# mcu.net
KiCad netlist of a schematic drawn in Altium Designer
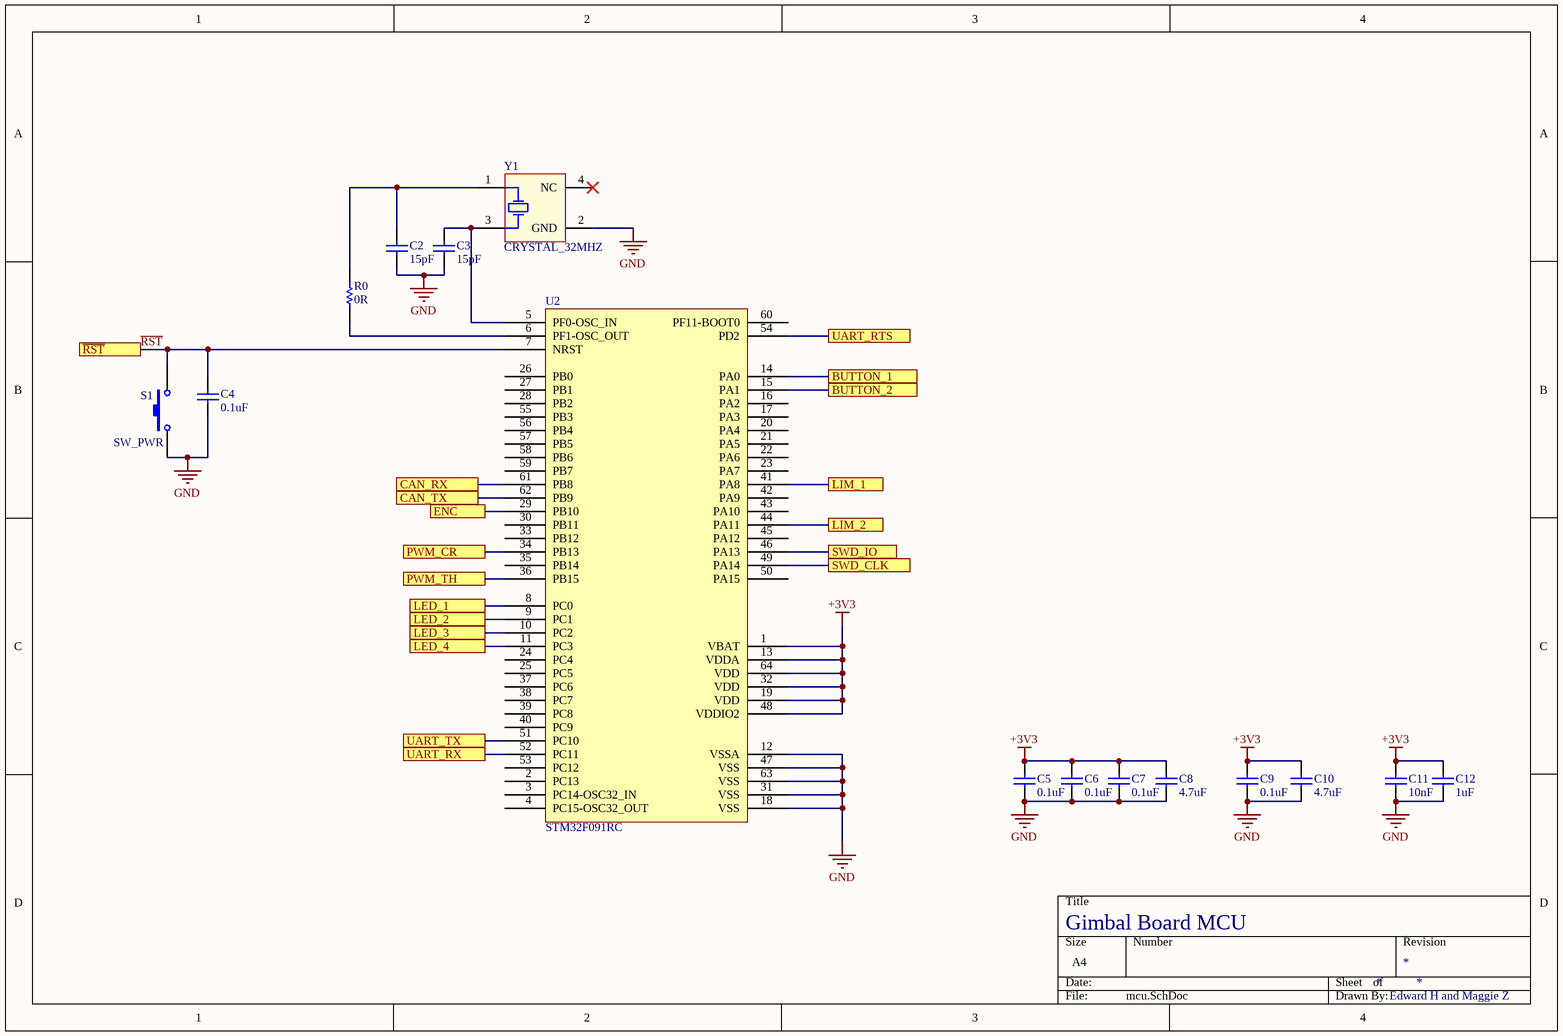
[diagram p0: mcu.SchDoc]

(export (version "E")
  (design (tool "Eeschema 10.0.6"))
  (components
    (comp (ref "C2")
      (value "15pF")
      (footprint "CAPC0603(1608)55_N")
      (description "CAP CER 15PF 250V NPO 0603")
      (fields (field (name "MANUFACTURER") "Yageo") (field (name "MPN") "AC0603JRNPOYBN150"))
      (libsource (lib "UWRT_Schematic_Library_2019") (part "CAP_15pF_0603"))
    )
    (comp (ref "C3")
      (value "15pF")
      (footprint "CAPC0603(1608)55_N")
      (description "CAP CER 15PF 250V NPO 0603")
      (fields (field (name "MANUFACTURER") "Yageo") (field (name "MPN") "AC0603JRNPOYBN150"))
      (libsource (lib "UWRT_Schematic_Library_2019") (part "CAP_15pF_0603"))
    )
    (comp (ref "C4")
      (value "0.1uF")
      (footprint "CAPC0603(1608)55_N")
      (description "CAP CER 0.1UF 16V X7R 0603")
      (fields (field (name "MANUFACTURER") "Yageo") (field (name "MPN") "CC0603KRX7R7BB104"))
      (libsource (lib "UWRT_Schematic_Library_2019") (part "CAP_0.1uF_16V_0603"))
    )
    (comp (ref "C5")
      (value "0.1uF")
      (footprint "CAPC0603(1608)55_N")
      (description "CAP CER 0.1UF 16V X7R 0603")
      (fields (field (name "MANUFACTURER") "Yageo") (field (name "MPN") "CC0603KRX7R7BB104"))
      (libsource (lib "UWRT_Schematic_Library_2019") (part "CAP_0.1uF_16V_0603"))
    )
    (comp (ref "C6")
      (value "0.1uF")
      (footprint "CAPC0603(1608)55_N")
      (description "CAP CER 0.1UF 16V X7R 0603")
      (fields (field (name "MANUFACTURER") "Yageo") (field (name "MPN") "CC0603KRX7R7BB104"))
      (libsource (lib "UWRT_Schematic_Library_2019") (part "CAP_0.1uF_16V_0603"))
    )
    (comp (ref "C7")
      (value "0.1uF")
      (footprint "CAPC0603(1608)55_N")
      (description "CAP CER 0.1UF 16V X7R 0603")
      (fields (field (name "MANUFACTURER") "Yageo") (field (name "MPN") "CC0603KRX7R7BB104"))
      (libsource (lib "UWRT_Schematic_Library_2019") (part "CAP_0.1uF_16V_0603"))
    )
    (comp (ref "C8")
      (value "4.7uF")
      (footprint "CAPC0603(1608)55_N")
      (description "CAP CER 4.7UF 6.3V X5R 0603")
      (fields (field (name "MANUFACTURER") "Yageo") (field (name "MPN") "CC0603KRX5R5BB475"))
      (libsource (lib "UWRT_Schematic_Library_2019") (part "CAP_4.7uF_0603"))
    )
    (comp (ref "C9")
      (value "0.1uF")
      (footprint "CAPC0603(1608)55_N")
      (description "CAP CER 0.1UF 16V X7R 0603")
      (fields (field (name "MANUFACTURER") "Yageo") (field (name "MPN") "CC0603KRX7R7BB104"))
      (libsource (lib "UWRT_Schematic_Library_2019") (part "CAP_0.1uF_16V_0603"))
    )
    (comp (ref "C10")
      (value "4.7uF")
      (footprint "CAPC0603(1608)55_N")
      (description "CAP CER 4.7UF 6.3V X5R 0603")
      (fields (field (name "MANUFACTURER") "Yageo") (field (name "MPN") "CC0603KRX5R5BB475"))
      (libsource (lib "UWRT_Schematic_Library_2019") (part "CAP_4.7uF_0603"))
    )
    (comp (ref "C11")
      (value "10nF")
      (footprint "CAPC0603(1608)55_N")
      (description "CAP CER 10000PF 16V X7R 0603")
      (fields (field (name "MANUFACTURER") "Yageo") (field (name "MPN") "CC0603KRX7R7BB103"))
      (libsource (lib "UWRT_Schematic_Library_2019") (part "CAP_10nF_0603"))
    )
    (comp (ref "C12")
      (value "1uF")
      (footprint "CAPC0603(1608)55_N")
      (description "CAP CER 1UF 16V Y5V 0603")
      (fields (field (name "MANUFACTURER") "Yageo") (field (name "MPN") "CC0603ZRY5V7BB105"))
      (libsource (lib "UWRT_Schematic_Library_2019") (part "CAP_1uF_16V_0603"))
    )
    (comp (ref "R0")
      (value "0R")
      (footprint "RESC0603(1608)_N")
      (description "RES SMD 0 OHM JUMPER 1/10W 0603")
      (fields (field (name "MANUFACTURER") "Yageo") (field (name "MPN") "RC0603JR-070RL"))
      (libsource (lib "UWRT_Schematic_Library_2019") (part "RES_0R_0603"))
    )
    (comp (ref "S1")
      (value "SW_PWR")
      (footprint "PTS830GM140")
      (description "Power Switch (Red)")
      (fields
        (field (name "MPN") "PTS830GM140 SMTR LFS")
        (field (name "DIGIKEY PART NUMBER") "CKN10587CT-ND")
      )
      (libsource (lib "UWRT_Schematic_Library_2019") (part "SW_PWR"))
    )
    (comp (ref "U2")
      (value "STM32F091RC")
      (footprint "UWRT_Footprint_Library_2019:STM_LQFP64_N")
      (fields
        (field (name "MANUFACTURER") "STMicroelectronics")
        (field (name "DIGIKEY PART NUMBER") "497-15167-ND")
      )
      (libsource (lib "UWRT_Schematic_Library_2019") (part "STM32F091RC"))
    )
    (comp (ref "Y1")
      (value "CRYSTAL_32MHZ")
      (footprint "AVX-CX2520DB32000D0GEJZ1-4_V")
      (description "CRYSTAL 32MHZ 8PF SMD")
      (fields
        (field (name "MANUFACTURER") "Kyocera International Inc. Electronic Components")
        (field (name "MPN") "CX2520DB32000D0GPSC1")
      )
      (libsource (lib "UWRT_Schematic_Library_2019") (part "CRYSTAL_32MHZ"))
    )
  )
  (nets
    (net (code "1") (name "+3V3") (class "Default")
      (node (ref "C10") (pin "2") (pinfunction "2_2") (pintype "passive"))
      (node (ref "C11") (pin "2") (pinfunction "2_2") (pintype "passive"))
      (node (ref "C12") (pin "2") (pinfunction "2_2") (pintype "passive"))
      (node (ref "C5") (pin "1") (pinfunction "1_1") (pintype "passive"))
      (node (ref "C6") (pin "1") (pinfunction "1_1") (pintype "passive"))
      (node (ref "C7") (pin "1") (pinfunction "1_1") (pintype "passive"))
      (node (ref "C8") (pin "2") (pinfunction "2_2") (pintype "passive"))
      (node (ref "C9") (pin "1") (pinfunction "1_1") (pintype "passive"))
      (node (ref "U2") (pin "1") (pinfunction "VBAT_1") (pintype "passive"))
      (node (ref "U2") (pin "13") (pinfunction "VDDA_13") (pintype "passive"))
      (node (ref "U2") (pin "19") (pinfunction "VDD_19") (pintype "passive"))
      (node (ref "U2") (pin "32") (pinfunction "VDD_32") (pintype "passive"))
      (node (ref "U2") (pin "48") (pinfunction "VDDIO2_48") (pintype "passive"))
      (node (ref "U2") (pin "64") (pinfunction "VDD_64") (pintype "passive"))
    )
    (net (code "2") (name "/BUTTON_1") (class "Default")
      (node (ref "U2") (pin "14") (pinfunction "PA0_14") (pintype "passive"))
    )
    (net (code "3") (name "/BUTTON_2") (class "Default")
      (node (ref "U2") (pin "15") (pinfunction "PA1_15") (pintype "passive"))
    )
    (net (code "4") (name "/CAN_RX") (class "Default")
      (node (ref "U2") (pin "61") (pinfunction "PB8_61") (pintype "passive"))
    )
    (net (code "5") (name "/CAN_TX") (class "Default")
      (node (ref "U2") (pin "62") (pinfunction "PB9_62") (pintype "passive"))
    )
    (net (code "6") (name "/ENC") (class "Default")
      (node (ref "U2") (pin "29") (pinfunction "PB10_29") (pintype "passive"))
    )
    (net (code "7") (name "/LED_1") (class "Default")
      (node (ref "U2") (pin "8") (pinfunction "PC0_8") (pintype "passive"))
    )
    (net (code "8") (name "/LED_2") (class "Default")
      (node (ref "U2") (pin "9") (pinfunction "PC1_9") (pintype "passive"))
    )
    (net (code "9") (name "/LED_3") (class "Default")
      (node (ref "U2") (pin "10") (pinfunction "PC2_10") (pintype "passive"))
    )
    (net (code "10") (name "/LED_4") (class "Default")
      (node (ref "U2") (pin "11") (pinfunction "PC3_11") (pintype "passive"))
    )
    (net (code "11") (name "/LIM_1") (class "Default")
      (node (ref "U2") (pin "41") (pinfunction "PA8_41") (pintype "passive"))
    )
    (net (code "12") (name "/LIM_2") (class "Default")
      (node (ref "U2") (pin "44") (pinfunction "PA11_44") (pintype "passive"))
    )
    (net (code "13") (name "/PWM_CR") (class "Default")
      (node (ref "U2") (pin "34") (pinfunction "PB13_34") (pintype "passive"))
    )
    (net (code "14") (name "/PWM_TH") (class "Default")
      (node (ref "U2") (pin "36") (pinfunction "PB15_36") (pintype "passive"))
    )
    (net (code "15") (name "/SWD_CLK") (class "Default")
      (node (ref "U2") (pin "49") (pinfunction "PA14_49") (pintype "passive"))
    )
    (net (code "16") (name "/SWD_IO") (class "Default")
      (node (ref "U2") (pin "46") (pinfunction "PA13_46") (pintype "passive"))
    )
    (net (code "17") (name "/UART_RTS") (class "Default")
      (node (ref "U2") (pin "54") (pinfunction "PD2_54") (pintype "passive"))
    )
    (net (code "18") (name "/UART_RX") (class "Default")
      (node (ref "U2") (pin "52") (pinfunction "PC11_52") (pintype "passive"))
    )
    (net (code "19") (name "/UART_TX") (class "Default")
      (node (ref "U2") (pin "51") (pinfunction "PC10_51") (pintype "passive"))
    )
    (net (code "20") (name "/~{RST}") (class "Default")
      (node (ref "C4") (pin "2") (pinfunction "2_2") (pintype "passive"))
      (node (ref "S1") (pin "2") (pinfunction "2_2") (pintype "passive"))
      (node (ref "U2") (pin "7") (pinfunction "NRST_7") (pintype "passive"))
    )
    (net (code "21") (name "GND") (class "Default")
      (node (ref "C10") (pin "1") (pinfunction "1_1") (pintype "passive"))
      (node (ref "C11") (pin "1") (pinfunction "1_1") (pintype "passive"))
      (node (ref "C12") (pin "1") (pinfunction "1_1") (pintype "passive"))
      (node (ref "C2") (pin "1") (pinfunction "1_1") (pintype "passive"))
      (node (ref "C3") (pin "1") (pinfunction "1_1") (pintype "passive"))
      (node (ref "C4") (pin "1") (pinfunction "1_1") (pintype "passive"))
      (node (ref "C5") (pin "2") (pinfunction "2_2") (pintype "passive"))
      (node (ref "C6") (pin "2") (pinfunction "2_2") (pintype "passive"))
      (node (ref "C7") (pin "2") (pinfunction "2_2") (pintype "passive"))
      (node (ref "C8") (pin "1") (pinfunction "1_1") (pintype "passive"))
      (node (ref "C9") (pin "2") (pinfunction "2_2") (pintype "passive"))
      (node (ref "S1") (pin "1") (pinfunction "1_1") (pintype "passive"))
      (node (ref "U2") (pin "12") (pinfunction "VSSA_12") (pintype "passive"))
      (node (ref "U2") (pin "18") (pinfunction "VSS_18") (pintype "passive"))
      (node (ref "U2") (pin "31") (pinfunction "VSS_31") (pintype "passive"))
      (node (ref "U2") (pin "47") (pinfunction "VSS_47") (pintype "passive"))
      (node (ref "U2") (pin "63") (pinfunction "VSS_63") (pintype "passive"))
      (node (ref "Y1") (pin "2") (pinfunction "GND_2") (pintype "power_in"))
    )
    (net (code "22") (name "Net-(C2-Pad2)") (class "Default")
      (node (ref "C2") (pin "2") (pinfunction "2_2") (pintype "passive"))
      (node (ref "R0") (pin "2") (pinfunction "2_2") (pintype "passive"))
      (node (ref "Y1") (pin "1") (pinfunction "HOT_1") (pintype "passive"))
    )
    (net (code "23") (name "Net-(U2-PF0-OSC_IN)") (class "Default")
      (node (ref "C3") (pin "2") (pinfunction "2_2") (pintype "passive"))
      (node (ref "U2") (pin "5") (pinfunction "PF0-OSC_IN_5") (pintype "passive"))
      (node (ref "Y1") (pin "3") (pinfunction "HOT_3") (pintype "passive"))
    )
    (net (code "24") (name "Net-(U2-PF1-OSC_OUT)") (class "Default")
      (node (ref "R0") (pin "1") (pinfunction "1_1") (pintype "passive"))
      (node (ref "U2") (pin "6") (pinfunction "PF1-OSC_OUT_6") (pintype "passive"))
    )
    (net (code "25") (name "unconnected-(U2-PA2-Pad16)") (class "Default")
      (node (ref "U2") (pin "16") (pinfunction "PA2_16") (pintype "passive"))
    )
    (net (code "26") (name "unconnected-(U2-PA3-Pad17)") (class "Default")
      (node (ref "U2") (pin "17") (pinfunction "PA3_17") (pintype "passive"))
    )
    (net (code "27") (name "unconnected-(U2-PA4-Pad20)") (class "Default")
      (node (ref "U2") (pin "20") (pinfunction "PA4_20") (pintype "passive"))
    )
    (net (code "28") (name "unconnected-(U2-PA5-Pad21)") (class "Default")
      (node (ref "U2") (pin "21") (pinfunction "PA5_21") (pintype "passive"))
    )
    (net (code "29") (name "unconnected-(U2-PA6-Pad22)") (class "Default")
      (node (ref "U2") (pin "22") (pinfunction "PA6_22") (pintype "passive"))
    )
    (net (code "30") (name "unconnected-(U2-PA7-Pad23)") (class "Default")
      (node (ref "U2") (pin "23") (pinfunction "PA7_23") (pintype "passive"))
    )
    (net (code "31") (name "unconnected-(U2-PA9-Pad42)") (class "Default")
      (node (ref "U2") (pin "42") (pinfunction "PA9_42") (pintype "passive"))
    )
    (net (code "32") (name "unconnected-(U2-PA10-Pad43)") (class "Default")
      (node (ref "U2") (pin "43") (pinfunction "PA10_43") (pintype "passive"))
    )
    (net (code "33") (name "unconnected-(U2-PA12-Pad45)") (class "Default")
      (node (ref "U2") (pin "45") (pinfunction "PA12_45") (pintype "passive"))
    )
    (net (code "34") (name "unconnected-(U2-PA15-Pad50)") (class "Default")
      (node (ref "U2") (pin "50") (pinfunction "PA15_50") (pintype "passive"))
    )
    (net (code "35") (name "unconnected-(U2-PB0-Pad26)") (class "Default")
      (node (ref "U2") (pin "26") (pinfunction "PB0_26") (pintype "passive"))
    )
    (net (code "36") (name "unconnected-(U2-PB1-Pad27)") (class "Default")
      (node (ref "U2") (pin "27") (pinfunction "PB1_27") (pintype "passive"))
    )
    (net (code "37") (name "unconnected-(U2-PB2-Pad28)") (class "Default")
      (node (ref "U2") (pin "28") (pinfunction "PB2_28") (pintype "passive"))
    )
    (net (code "38") (name "unconnected-(U2-PB3-Pad55)") (class "Default")
      (node (ref "U2") (pin "55") (pinfunction "PB3_55") (pintype "passive"))
    )
    (net (code "39") (name "unconnected-(U2-PB4-Pad56)") (class "Default")
      (node (ref "U2") (pin "56") (pinfunction "PB4_56") (pintype "passive"))
    )
    (net (code "40") (name "unconnected-(U2-PB5-Pad57)") (class "Default")
      (node (ref "U2") (pin "57") (pinfunction "PB5_57") (pintype "passive"))
    )
    (net (code "41") (name "unconnected-(U2-PB6-Pad58)") (class "Default")
      (node (ref "U2") (pin "58") (pinfunction "PB6_58") (pintype "passive"))
    )
    (net (code "42") (name "unconnected-(U2-PB7-Pad59)") (class "Default")
      (node (ref "U2") (pin "59") (pinfunction "PB7_59") (pintype "passive"))
    )
    (net (code "43") (name "unconnected-(U2-PB11-Pad30)") (class "Default")
      (node (ref "U2") (pin "30") (pinfunction "PB11_30") (pintype "passive"))
    )
    (net (code "44") (name "unconnected-(U2-PB12-Pad33)") (class "Default")
      (node (ref "U2") (pin "33") (pinfunction "PB12_33") (pintype "passive"))
    )
    (net (code "45") (name "unconnected-(U2-PB14-Pad35)") (class "Default")
      (node (ref "U2") (pin "35") (pinfunction "PB14_35") (pintype "passive"))
    )
    (net (code "46") (name "unconnected-(U2-PC4-Pad24)") (class "Default")
      (node (ref "U2") (pin "24") (pinfunction "PC4_24") (pintype "passive"))
    )
    (net (code "47") (name "unconnected-(U2-PC5-Pad25)") (class "Default")
      (node (ref "U2") (pin "25") (pinfunction "PC5_25") (pintype "passive"))
    )
    (net (code "48") (name "unconnected-(U2-PC6-Pad37)") (class "Default")
      (node (ref "U2") (pin "37") (pinfunction "PC6_37") (pintype "passive"))
    )
    (net (code "49") (name "unconnected-(U2-PC7-Pad38)") (class "Default")
      (node (ref "U2") (pin "38") (pinfunction "PC7_38") (pintype "passive"))
    )
    (net (code "50") (name "unconnected-(U2-PC8-Pad39)") (class "Default")
      (node (ref "U2") (pin "39") (pinfunction "PC8_39") (pintype "passive"))
    )
    (net (code "51") (name "unconnected-(U2-PC9-Pad40)") (class "Default")
      (node (ref "U2") (pin "40") (pinfunction "PC9_40") (pintype "passive"))
    )
    (net (code "52") (name "unconnected-(U2-PC12-Pad53)") (class "Default")
      (node (ref "U2") (pin "53") (pinfunction "PC12_53") (pintype "passive"))
    )
    (net (code "53") (name "unconnected-(U2-PC13-Pad2)") (class "Default")
      (node (ref "U2") (pin "2") (pinfunction "PC13_2") (pintype "passive"))
    )
    (net (code "54") (name "unconnected-(U2-PC14-OSC32_IN-Pad3)") (class "Default")
      (node (ref "U2") (pin "3") (pinfunction "PC14-OSC32_IN_3") (pintype "passive"))
    )
    (net (code "55") (name "unconnected-(U2-PC15-OSC32_OUT-Pad4)") (class "Default")
      (node (ref "U2") (pin "4") (pinfunction "PC15-OSC32_OUT_4") (pintype "passive"))
    )
    (net (code "56") (name "unconnected-(U2-PF11-BOOT0-Pad60)") (class "Default")
      (node (ref "U2") (pin "60") (pinfunction "PF11-BOOT0_60") (pintype "passive"))
    )
    (net (code "57") (name "unconnected-(Y1-NC-Pad4)") (class "Default")
      (node (ref "Y1") (pin "4") (pinfunction "NC_4") (pintype "passive+no_connect"))
    )
  )
)
